# Voltage_Regulator.net
KiCad netlist of a schematic drawn in Altium Designer
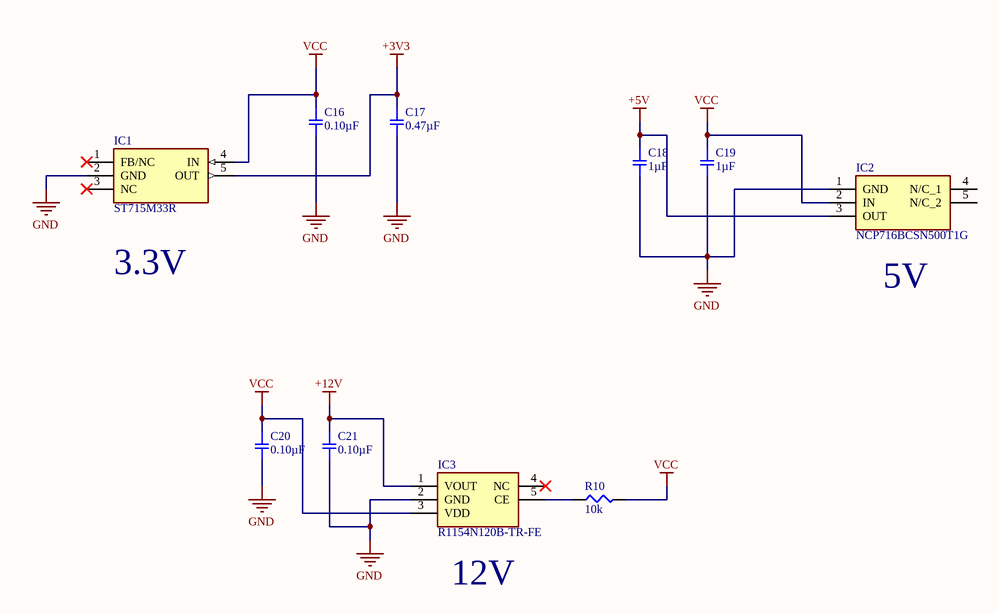
[diagram p0: Voltage Regulator.SchDoc]

(export (version "E")
  (design (tool "Eeschema 10.0.6"))
  (components
    (comp (ref "C16")
      (value "0.10µF")
      (footprint "SMD-0402C")
      (description "CAP CER 0.1UF 16V X7R 0402")
      (fields
        (field (name "DIGI-KEY PART NUMBER") "490-4759-1-ND")
        (field (name "PART NUMBER") "GCM155R71C104KA55D")
      )
      (libsource (lib "capacitor_murata_0402") (part "GCM155R71C104KA55D"))
    )
    (comp (ref "C17")
      (value "0.47µF")
      (footprint "SMD-0402C")
      (description "CAP CER 0.47UF 16V X5R 0402")
      (fields
        (field (name "DIGI-KEY PART NUMBER") "490-13421-1-ND")
        (field (name "PART NUMBER") "GRM155R61C474KE01D")
      )
      (libsource (lib "capacitor_murata_0402") (part "GRM155R61C474KE01D"))
    )
    (comp (ref "C18")
      (value "1µF")
      (footprint "SMD-0402C")
      (description "CAP CER 1UF 16V X6S 0402")
      (fields
        (field (name "DIGI-KEY PART NUMBER") "490-12700-1-ND")
        (field (name "PART NUMBER") "GRM155C81C105KE11D")
      )
      (libsource (lib "capacitor_murata_0402") (part "GRM155C81C105KE11D"))
    )
    (comp (ref "C19")
      (value "1µF")
      (footprint "SMD-0402C")
      (description "CAP CER 1UF 16V X6S 0402")
      (fields
        (field (name "DIGI-KEY PART NUMBER") "490-12700-1-ND")
        (field (name "PART NUMBER") "GRM155C81C105KE11D")
      )
      (libsource (lib "capacitor_murata_0402") (part "GRM155C81C105KE11D"))
    )
    (comp (ref "C20")
      (value "0.10µF")
      (footprint "SMD-0402C")
      (description "CAP CER 0.1UF 16V X7R 0402")
      (fields
        (field (name "DIGI-KEY PART NUMBER") "490-4759-1-ND")
        (field (name "PART NUMBER") "GCM155R71C104KA55D")
      )
      (libsource (lib "capacitor_murata_0402") (part "GCM155R71C104KA55D"))
    )
    (comp (ref "C21")
      (value "0.10µF")
      (footprint "SMD-0402C")
      (description "CAP CER 0.1UF 16V X7R 0402")
      (fields
        (field (name "DIGI-KEY PART NUMBER") "490-4759-1-ND")
        (field (name "PART NUMBER") "GCM155R71C104KA55D")
      )
      (libsource (lib "capacitor_murata_0402") (part "GCM155R71C104KA55D"))
    )
    (comp (ref "IC1")
      (value "ST715M33R")
      (footprint "SamacSys:SOT95P280X145-5N")
      (description "Integrated Circuit")
      (fields (field (name "MOUSER PART NUMBER") "511-ST715M33R"))
      (libsource (lib "*") (part "ST715M33R"))
    )
    (comp (ref "IC2")
      (value "NCP716BCSN500T1G")
      (footprint "SamacSys:SOT95P275X110-5N")
      (description "Integrated Circuit")
      (fields (field (name "MOUSER PART NUMBER") "863-NCP716BCSN500T1G"))
      (libsource (lib "*") (part "NCP716BCSN500T1G"))
    )
    (comp (ref "IC3")
      (value "R1154N120B-TR-FE")
      (footprint "SamacSys:SOT95P280X130-5N")
      (description "Integrated Circuit")
      (fields (field (name "MOUSER PART NUMBER") "848-R1154N120BTRFE"))
      (libsource (lib "*") (part "R1154N120B-TR-FE"))
    )
    (comp (ref "R10")
      (value "10k")
      (footprint "SMD-0402-RES")
      (description "RES SMD 10K OHM 5% 1/10W 0402")
      (fields (field (name "PART NUMBER") "ERJ-2GEJ103X") (field (name "DIGI-KEY PART NUMBER") "P10KJCT-ND"))
      (libsource (lib "Panasonic_ERJ_0402") (part "ERJ-2GEJ103X"))
    )
  )
  (nets
    (net (code "1") (name "+3V3") (class "Default")
      (node (ref "C17") (pin "1") (pinfunction "1_1") (pintype "passive"))
      (node (ref "IC1") (pin "5") (pinfunction "OUT_5") (pintype "output"))
    )
    (net (code "2") (name "+5V") (class "Default")
      (node (ref "C18") (pin "1") (pinfunction "1_1") (pintype "passive"))
      (node (ref "IC2") (pin "3") (pinfunction "OUT_3") (pintype "passive"))
    )
    (net (code "3") (name "+12V") (class "Default")
      (node (ref "C21") (pin "1") (pinfunction "1_1") (pintype "passive"))
      (node (ref "IC3") (pin "1") (pinfunction "VOUT_1") (pintype "passive"))
    )
    (net (code "4") (name "GND") (class "Default")
      (node (ref "C16") (pin "2") (pinfunction "2_2") (pintype "passive"))
      (node (ref "C17") (pin "2") (pinfunction "2_2") (pintype "passive"))
      (node (ref "C18") (pin "2") (pinfunction "2_2") (pintype "passive"))
      (node (ref "C19") (pin "2") (pinfunction "2_2") (pintype "passive"))
      (node (ref "C20") (pin "2") (pinfunction "2_2") (pintype "passive"))
      (node (ref "C21") (pin "2") (pinfunction "2_2") (pintype "passive"))
      (node (ref "IC1") (pin "2") (pinfunction "GND_2") (pintype "power_in"))
      (node (ref "IC2") (pin "1") (pinfunction "GND_1") (pintype "passive"))
      (node (ref "IC3") (pin "2") (pinfunction "GND_2") (pintype "passive"))
    )
    (net (code "5") (name "Net-(IC3-CE)") (class "Default")
      (node (ref "IC3") (pin "5") (pinfunction "CE_5") (pintype "passive"))
      (node (ref "R10") (pin "1") (pinfunction "1_1") (pintype "passive"))
    )
    (net (code "6") (name "VCC") (class "Default")
      (node (ref "C16") (pin "1") (pinfunction "1_1") (pintype "passive"))
      (node (ref "C19") (pin "1") (pinfunction "1_1") (pintype "passive"))
      (node (ref "C20") (pin "1") (pinfunction "1_1") (pintype "passive"))
      (node (ref "IC1") (pin "4") (pinfunction "IN_4") (pintype "input"))
      (node (ref "IC2") (pin "2") (pinfunction "IN_2") (pintype "passive"))
      (node (ref "IC3") (pin "3") (pinfunction "VDD_3") (pintype "passive"))
      (node (ref "R10") (pin "2") (pinfunction "2_2") (pintype "passive"))
    )
    (net (code "7") (name "unconnected-(IC1-FB{slash}NC-Pad1)") (class "Default")
      (node (ref "IC1") (pin "1") (pinfunction "FB/NC_1") (pintype "passive+no_connect"))
    )
    (net (code "8") (name "unconnected-(IC1-NC-Pad3)") (class "Default")
      (node (ref "IC1") (pin "3") (pinfunction "NC_3") (pintype "passive+no_connect"))
    )
    (net (code "9") (name "unconnected-(IC2-N{slash}C_1-Pad4)") (class "Default")
      (node (ref "IC2") (pin "4") (pinfunction "N/C_1_4") (pintype "passive"))
    )
    (net (code "10") (name "unconnected-(IC2-N{slash}C_2-Pad5)") (class "Default")
      (node (ref "IC2") (pin "5") (pinfunction "N/C_2_5") (pintype "passive"))
    )
    (net (code "11") (name "unconnected-(IC3-NC-Pad4)") (class "Default")
      (node (ref "IC3") (pin "4") (pinfunction "NC_4") (pintype "passive+no_connect"))
    )
  )
)
